# Instrumentation_Amplifier.net
KiCad netlist of a schematic drawn in Altium Designer
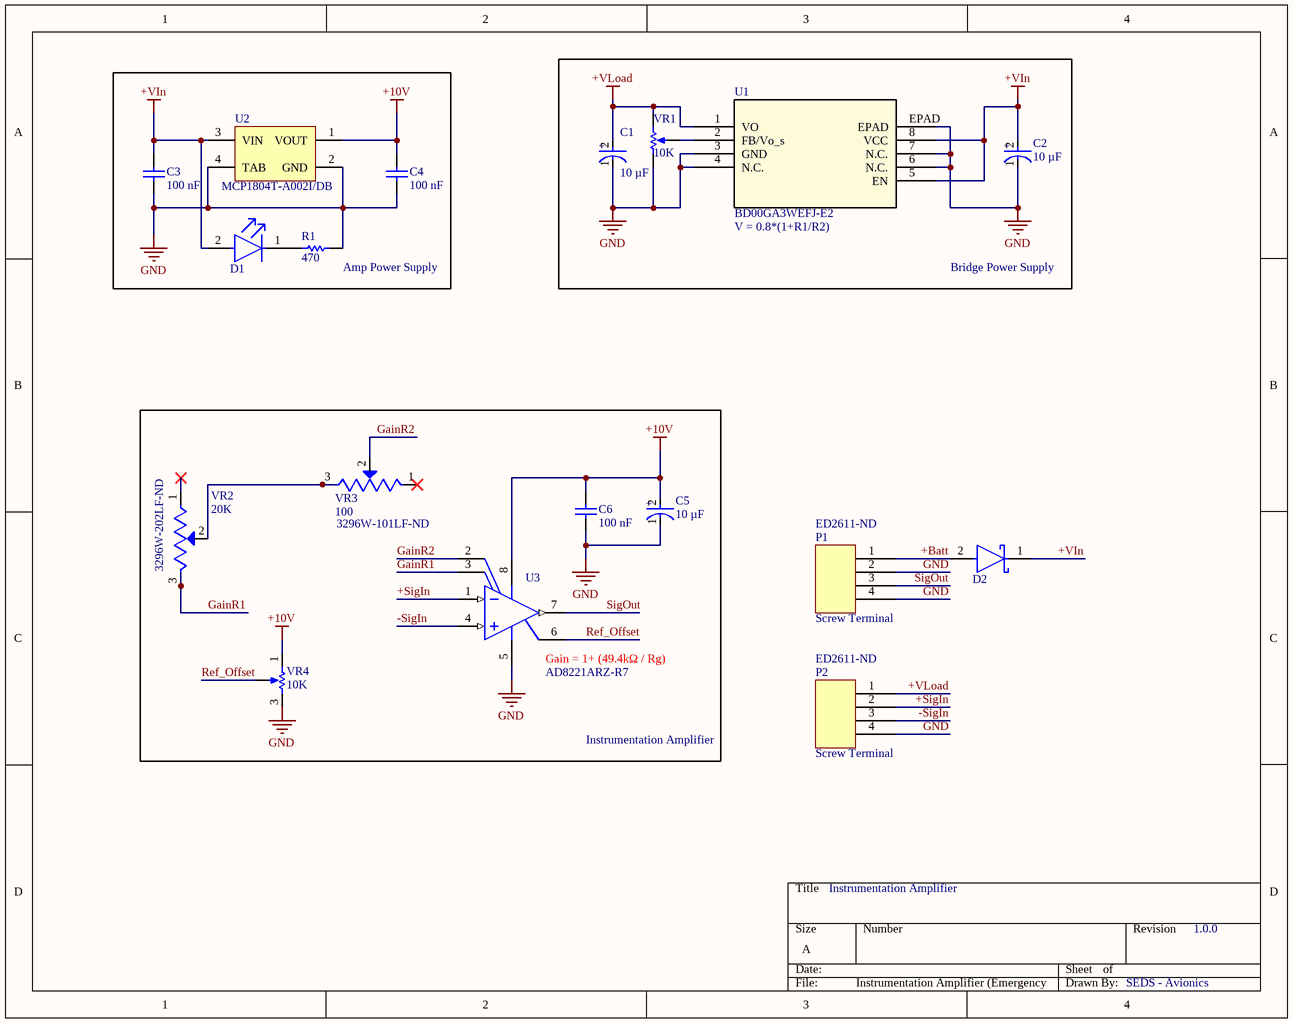
[diagram p0: Instrumentation Amplifier (Emergency Version).SchDoc]

(export (version "E")
  (design (tool "Eeschema 10.0.6"))
  (components
    (comp (ref "C1")
      (value "10 µF")
      (footprint "FP-TAP106K016SCS-MFG")
      (description "CAP TANT 10UF 10% 16V RADIAL")
      (fields (field (name "TOLERANCE") "10%") (field (name "VOLTAGE") "16V"))
      (libsource (lib "Altium Content Vault") (part "cf48714ba7e38822c1575c7ec0b6d1f"))
    )
    (comp (ref "C2")
      (value "10 µF")
      (footprint "FP-TAP106K016SCS-MFG")
      (description "CAP TANT 10UF 10% 16V RADIAL")
      (fields (field (name "TOLERANCE") "10%") (field (name "VOLTAGE") "16V"))
      (libsource (lib "Altium Content Vault") (part "cf48714ba7e38822c1575c7ec0b6d1f"))
    )
    (comp (ref "C3")
      (value "100 nF")
      (footprint "CAPC1608X95X40ML15T15")
      (fields (field (name "MANUFACTURER") "Vitramon") (field (name "PART NUMBER") "VJ0603Y104KXQCW1BC"))
      (libsource (lib "Altium Content Vault") (part "CAP"))
    )
    (comp (ref "C4")
      (value "100 nF")
      (footprint "CAPC1608X95X40ML15T15")
      (fields (field (name "MANUFACTURER") "Vitramon") (field (name "PART NUMBER") "VJ0603Y104KXQCW1BC"))
      (libsource (lib "Altium Content Vault") (part "CAP"))
    )
    (comp (ref "C5")
      (value "10 µF")
      (footprint "FP-TAP106K016SCS-MFG")
      (description "CAP TANT 10UF 10% 16V RADIAL")
      (fields (field (name "TOLERANCE") "10%") (field (name "VOLTAGE") "16V"))
      (libsource (lib "Altium Content Vault") (part "cf48714ba7e38822c1575c7ec0b6d1f"))
    )
    (comp (ref "C6")
      (value "100 nF")
      (footprint "CAPC1608X95X40ML15T15")
      (fields (field (name "MANUFACTURER") "Vitramon") (field (name "PART NUMBER") "VJ0603Y104KXQCW1BC"))
      (libsource (lib "Altium Content Vault") (part "CAP"))
    )
    (comp (ref "D1")
      (value "LTST-C191KGKT")
      (footprint "FP-LTST-C191KGKT-MFG")
      (description "LED GREEN CLEAR SMD")
      (libsource (lib "Altium Content Vault") (part "8706943c75ba83719d021d2fdc84c58"))
    )
    (comp (ref "D2")
      (value "VS-10BQ015-M3/5BT")
      (footprint "FP-95401-MFG")
      (description "DIODE SCHOTTKY 15V 1A DO214AA")
      (fields
        (field (name "OCTOPART") "https://octopart.com/vs-10bq015-m3%2F5bt-vishay-39003459")
        (field (name "MANUFACTURER") "Vishay")
      )
      (libsource (lib "Altium Content Vault") (part "1d6ec82d83fb6aee721767c19dac4b9"))
    )
    (comp (ref "P1")
      (value "Screw Terminal")
      (footprint "Screw Terminal")
      (description "Conn Terminal Block 4 POS 5.08mm Solder ST Thru-Hole 15A")
      (fields
        (field (name "SUPPLIER PART NUMBER 1") "ED2611-ND")
        (field (name "MANUFACTURER") "On-Shore Technology")
        (field (name "MANUFACTURER PART NUMBER") "OSTTC042162")
      )
      (libsource (lib "ScrewTerminal") (part "Screw Terminal"))
    )
    (comp (ref "P2")
      (value "Screw Terminal")
      (footprint "Screw Terminal")
      (description "Conn Terminal Block 4 POS 5.08mm Solder ST Thru-Hole 15A")
      (fields
        (field (name "SUPPLIER PART NUMBER 1") "ED2611-ND")
        (field (name "MANUFACTURER") "On-Shore Technology")
        (field (name "MANUFACTURER PART NUMBER") "OSTTC042162")
      )
      (libsource (lib "ScrewTerminal") (part "Screw Terminal"))
    )
    (comp (ref "R1")
      (value "470")
      (footprint "RESC1608X55X30NL15T15")
      (description "ERJ-3GEYJ471V")
      (fields (field (name "MANUFACTURER") "Panasonic"))
      (libsource (lib "Altium Content Vault") (part "RES"))
    )
    (comp (ref "U1")
      (value "BD00GA3WEFJ-E2")
      (footprint "HTSOP-J8_ROM")
      (description "IC REG LDO ADJ 0.3A 8HTSOP-J")
      (fields
        (field (name "MANUFACTURER") "Rohm")
        (field (name "COPYRIGHT") "Copyright (C) 2022 Ultra Librarian. All rights reserved.")
      )
      (libsource (lib "BD00GA3WEFJ-E2") (part "BD00GA3WEFJ-E2"))
    )
    (comp (ref "U2")
      (value "MCP1804T-A002I/DB")
      (footprint "SOT-223-DB3_N")
      (description "150 mA, 28V LDO Regulator With Shutdown, 3-Pin SOT-223, Industrial Temperature, Tape and Reel")
      (libsource (lib "Altium Content Vault") (part "PM-LINEREG-MCP1804T-SOT4"))
    )
    (comp (ref "U3")
      (value "AD8221ARZ-R7")
      (footprint "ADI-R-8_M")
      (fields (field (name "MANUFACTURER") "Analog Devices"))
      (libsource (lib "Altium Content Vault") (part "ADI-AD8221-8"))
    )
    (comp (ref "VR1")
      (value "10K")
      (footprint "BOUR-3296W")
      (fields (field (name "TOLERANCE") "1%"))
      (libsource (lib "") (part "RES-POT-3_1"))
    )
    (comp (ref "VR2")
      (value "20K")
      (footprint "TRIM_3296W-1-202LF")
      (description "Trimmer Potentiometer 2k Ohm 10% 1/2 Watt 25 Turn 2.19mm Pin Through Hole")
      (fields
        (field (name "MF") "Bourns")
        (field (name "MP") "3296W-1-202LF")
        (field (name "SUPPLIER PART NUMBER 1") "3296W-202LF-ND")
      )
      (libsource (lib "3296W-1-202LF") (part "3296W-1-202LF"))
    )
    (comp (ref "VR3")
      (value "100")
      (footprint "TRIM_3296W-1-101LF")
      (description "Res Cermet Trimmer 100 Ohm 10% 1/2W 25(Elec)Turn 2.19mm (9.53 X 4.83 X 11.55mm) Pin Thru-Hole Tube")
      (fields
        (field (name "MP") "3296W-1-101LF")
        (field (name "MF") "Bourns")
        (field (name "SUPPLIER PART NUMBER 1") "3296W-101LF-ND")
      )
      (libsource (lib "3296W-1-101LF") (part "3296W-1-101LF"))
    )
    (comp (ref "VR4")
      (value "10K")
      (footprint "BOUR-3296W")
      (fields (field (name "TOLERANCE") "1%"))
      (libsource (lib "Altium Content Vault") (part "RES-POT-3"))
    )
  )
  (nets
    (net (code "1") (name "+10V") (class "Default")
      (node (ref "C4") (pin "2") (pinfunction "2_2") (pintype "passive"))
      (node (ref "C5") (pin "2") (pinfunction "A_2") (pintype "passive"))
      (node (ref "C6") (pin "2") (pinfunction "2_2") (pintype "passive"))
      (node (ref "U2") (pin "1") (pinfunction "VOUT_1") (pintype "power_in"))
      (node (ref "U3") (pin "8") (pinfunction "VS+_8") (pintype "power_in"))
      (node (ref "VR4") (pin "1") (pinfunction "CCW_1") (pintype "passive"))
    )
    (net (code "2") (name "+VIn") (class "Default")
      (node (ref "C2") (pin "2") (pinfunction "A_2") (pintype "passive"))
      (node (ref "C3") (pin "2") (pinfunction "2_2") (pintype "passive"))
      (node (ref "D1") (pin "2") (pinfunction "A_2") (pintype "passive"))
      (node (ref "D2") (pin "1") (pinfunction "C_1") (pintype "passive"))
      (node (ref "U1") (pin "5") (pinfunction "EN_5") (pintype "passive"))
      (node (ref "U1") (pin "8") (pinfunction "VCC_8") (pintype "power_in"))
      (node (ref "U2") (pin "3") (pinfunction "VIN_3") (pintype "power_in"))
    )
    (net (code "3") (name "+VLoad") (class "Default")
      (node (ref "C1") (pin "2") (pinfunction "A_2") (pintype "passive"))
      (node (ref "P2") (pin "1") (pinfunction "Pin1_1") (pintype "passive"))
      (node (ref "U1") (pin "1") (pinfunction "VO_1") (pintype "passive"))
      (node (ref "VR1") (pin "3") (pinfunction "CW_3") (pintype "passive"))
    )
    (net (code "4") (name "/+Batt") (class "Default")
      (node (ref "D2") (pin "2") (pinfunction "A_2") (pintype "passive"))
      (node (ref "P1") (pin "1") (pinfunction "Pin1_1") (pintype "passive"))
    )
    (net (code "5") (name "/+SigIn") (class "Default")
      (node (ref "P2") (pin "2") (pinfunction "Pin2_2") (pintype "passive"))
      (node (ref "U3") (pin "1") (pinfunction "IN-_1") (pintype "input"))
    )
    (net (code "6") (name "/-SigIn") (class "Default")
      (node (ref "P2") (pin "3") (pinfunction "Pin3_3") (pintype "passive"))
      (node (ref "U3") (pin "4") (pinfunction "IN+_4") (pintype "input"))
    )
    (net (code "7") (name "/GainR1") (class "Default")
      (node (ref "U3") (pin "3") (pinfunction "RG_3") (pintype "passive"))
      (node (ref "VR2") (pin "3") (pinfunction "CW_3") (pintype "passive"))
    )
    (net (code "8") (name "/GainR2") (class "Default")
      (node (ref "U3") (pin "2") (pinfunction "RG_2") (pintype "passive"))
      (node (ref "VR3") (pin "2") (pinfunction "WIPER_2") (pintype "passive"))
    )
    (net (code "9") (name "/Ref_Offset") (class "Default")
      (node (ref "U3") (pin "6") (pinfunction "REF_6") (pintype "passive"))
      (node (ref "VR4") (pin "2") (pinfunction "S_2") (pintype "passive"))
    )
    (net (code "10") (name "/SigOut") (class "Default")
      (node (ref "P1") (pin "3") (pinfunction "Pin3_3") (pintype "passive"))
      (node (ref "U3") (pin "7") (pinfunction "VOUT_7") (pintype "output"))
    )
    (net (code "11") (name "GND") (class "Default")
      (node (ref "C1") (pin "1") (pinfunction "C_1") (pintype "passive"))
      (node (ref "C2") (pin "1") (pinfunction "C_1") (pintype "passive"))
      (node (ref "C3") (pin "1") (pinfunction "1_1") (pintype "passive"))
      (node (ref "C4") (pin "1") (pinfunction "1_1") (pintype "passive"))
      (node (ref "C5") (pin "1") (pinfunction "C_1") (pintype "passive"))
      (node (ref "C6") (pin "1") (pinfunction "1_1") (pintype "passive"))
      (node (ref "P1") (pin "2") (pinfunction "Pin2_2") (pintype "passive"))
      (node (ref "P1") (pin "4") (pinfunction "Pin4_4") (pintype "passive"))
      (node (ref "P2") (pin "4") (pinfunction "Pin4_4") (pintype "passive"))
      (node (ref "R1") (pin "2") (pinfunction "2_2") (pintype "passive"))
      (node (ref "U1") (pin "3") (pinfunction "GND_3") (pintype "passive"))
      (node (ref "U1") (pin "4") (pinfunction "N.C._4") (pintype "passive"))
      (node (ref "U1") (pin "6") (pinfunction "N.C._6") (pintype "passive"))
      (node (ref "U1") (pin "7") (pinfunction "N.C._7") (pintype "passive"))
      (node (ref "U1") (pin "EPAD") (pinfunction "EPAD_EPAD") (pintype "passive"))
      (node (ref "U2") (pin "2") (pinfunction "GND_2") (pintype "power_in"))
      (node (ref "U2") (pin "4") (pinfunction "TAB_4") (pintype "power_in"))
      (node (ref "U3") (pin "5") (pinfunction "VS-_5") (pintype "power_in"))
      (node (ref "VR1") (pin "1") (pinfunction "CCW_1") (pintype "passive"))
      (node (ref "VR4") (pin "3") (pinfunction "CW_3") (pintype "passive"))
    )
    (net (code "12") (name "Net-(D1-C)") (class "Default")
      (node (ref "D1") (pin "1") (pinfunction "C_1") (pintype "passive"))
      (node (ref "R1") (pin "1") (pinfunction "1_1") (pintype "passive"))
    )
    (net (code "13") (name "Net-(U1-FB{slash}Vo_s)") (class "Default")
      (node (ref "U1") (pin "2") (pinfunction "FB/Vo_s_2") (pintype "passive"))
      (node (ref "VR1") (pin "2") (pinfunction "S_2") (pintype "passive"))
    )
    (net (code "14") (name "Net-(VR2-WIPER)") (class "Default")
      (node (ref "VR2") (pin "2") (pinfunction "WIPER_2") (pintype "passive"))
      (node (ref "VR3") (pin "3") (pinfunction "CW_3") (pintype "passive"))
    )
    (net (code "15") (name "unconnected-(VR2-CCW-Pad1)") (class "Default")
      (node (ref "VR2") (pin "1") (pinfunction "CCW_1") (pintype "passive+no_connect"))
    )
    (net (code "16") (name "unconnected-(VR3-CCW-Pad1)") (class "Default")
      (node (ref "VR3") (pin "1") (pinfunction "CCW_1") (pintype "passive+no_connect"))
    )
  )
)
